# EMG_EEG_PreAmp_Alpha1b.net
KiCad netlist of a schematic drawn in EAGLE
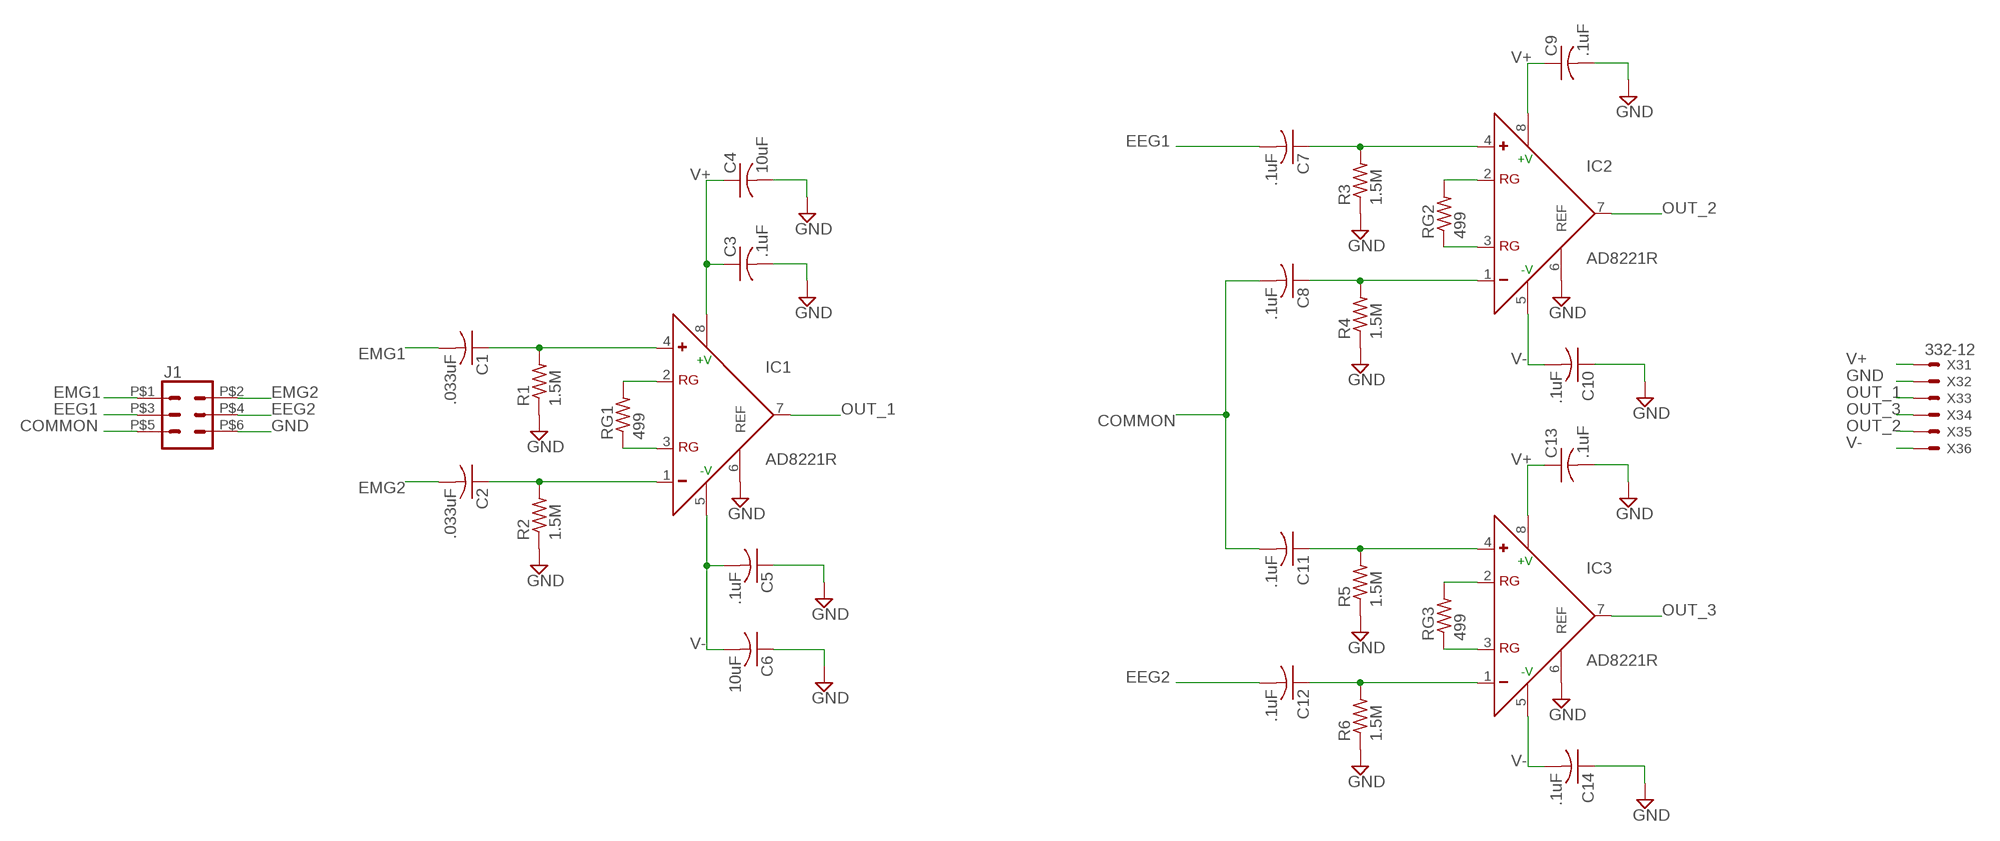
[diagram p0: schematic, sheet 1]

(export (version "E")
  (design (tool "Eeschema 10.0.6"))
  (components
    (comp (ref "C1")
      (value ".033uF")
      (footprint "eagle-import:C0805K")
      (libsource (lib "eagle-import") (part "C-USC0805K"))
    )
    (comp (ref "C2")
      (value ".033uF")
      (footprint "eagle-import:C0805K")
      (libsource (lib "eagle-import") (part "C-USC0805K"))
    )
    (comp (ref "C3")
      (value ".1uF")
      (footprint "eagle-import:C0805K")
      (libsource (lib "eagle-import") (part "C-USC0805K"))
    )
    (comp (ref "C4")
      (value "10uF")
      (footprint "eagle-import:C0805K")
      (libsource (lib "eagle-import") (part "C-USC0805K"))
    )
    (comp (ref "C5")
      (value ".1uF")
      (footprint "eagle-import:C0805K")
      (libsource (lib "eagle-import") (part "C-USC0805K"))
    )
    (comp (ref "C6")
      (value "10uF")
      (footprint "eagle-import:C0805K")
      (libsource (lib "eagle-import") (part "C-USC0805K"))
    )
    (comp (ref "C7")
      (value ".1uF")
      (footprint "eagle-import:C0805K")
      (libsource (lib "eagle-import") (part "C-USC0805K"))
    )
    (comp (ref "C8")
      (value ".1uF")
      (footprint "eagle-import:C0805K")
      (libsource (lib "eagle-import") (part "C-USC0805K"))
    )
    (comp (ref "C9")
      (value ".1uF")
      (footprint "eagle-import:C0805K")
      (libsource (lib "eagle-import") (part "C-USC0805K"))
    )
    (comp (ref "C10")
      (value ".1uF")
      (footprint "eagle-import:C0805K")
      (libsource (lib "eagle-import") (part "C-USC0805K"))
    )
    (comp (ref "C11")
      (value ".1uF")
      (footprint "eagle-import:C0805K")
      (libsource (lib "eagle-import") (part "C-USC0805K"))
    )
    (comp (ref "C12")
      (value ".1uF")
      (footprint "eagle-import:C0805K")
      (libsource (lib "eagle-import") (part "C-USC0805K"))
    )
    (comp (ref "C13")
      (value ".1uF")
      (footprint "eagle-import:C0805K")
      (libsource (lib "eagle-import") (part "C-USC0805K"))
    )
    (comp (ref "C14")
      (value ".1uF")
      (footprint "eagle-import:C0805K")
      (libsource (lib "eagle-import") (part "C-USC0805K"))
    )
    (comp (ref "IC1")
      (value "AD8221R")
      (footprint "eagle-import:SO8")
      (fields (field (name "MPN") "AD620AR"))
      (libsource (lib "eagle-import") (part "AD8221R"))
    )
    (comp (ref "IC2")
      (value "AD8221R")
      (footprint "eagle-import:SO8")
      (fields (field (name "MPN") "AD620AR"))
      (libsource (lib "eagle-import") (part "AD8221R"))
    )
    (comp (ref "IC3")
      (value "AD8221R")
      (footprint "eagle-import:SO8")
      (fields (field (name "MPN") "AD620AR"))
      (libsource (lib "eagle-import") (part "AD8221R"))
    )
    (comp (ref "J1")
      (value "2X3MILL-MAX")
      (footprint "eagle-import:2X3_MILL-MAX_853")
      (libsource (lib "eagle-import") (part "2X3MILL-MAX"))
    )
    (comp (ref "R1")
      (value "1.5M")
      (footprint "eagle-import:R0805")
      (libsource (lib "eagle-import") (part "R-US_R0805"))
    )
    (comp (ref "R2")
      (value "1.5M")
      (footprint "eagle-import:R0805")
      (libsource (lib "eagle-import") (part "R-US_R0805"))
    )
    (comp (ref "R3")
      (value "1.5M")
      (footprint "eagle-import:R0805")
      (libsource (lib "eagle-import") (part "R-US_R0805"))
    )
    (comp (ref "R4")
      (value "1.5M")
      (footprint "eagle-import:R0805")
      (libsource (lib "eagle-import") (part "R-US_R0805"))
    )
    (comp (ref "R5")
      (value "1.5M")
      (footprint "eagle-import:R0805")
      (libsource (lib "eagle-import") (part "R-US_R0805"))
    )
    (comp (ref "R6")
      (value "1.5M")
      (footprint "eagle-import:R0805")
      (libsource (lib "eagle-import") (part "R-US_R0805"))
    )
    (comp (ref "RG1")
      (value "499")
      (footprint "eagle-import:R0805")
      (libsource (lib "eagle-import") (part "R-US_R0805"))
    )
    (comp (ref "RG2")
      (value "499")
      (footprint "eagle-import:R0805")
      (libsource (lib "eagle-import") (part "R-US_R0805"))
    )
    (comp (ref "RG3")
      (value "499")
      (footprint "eagle-import:R0805")
      (libsource (lib "eagle-import") (part "R-US_R0805"))
    )
    (comp (ref "X3")
      (value "332-12")
      (footprint "eagle-import:1X6_WITH_STRAIN_RELIEF")
      (libsource (lib "eagle-import") (part "332-12"))
    )
  )
  (nets
    (net (code "1") (name "/COMMON") (class "Default")
      (node (ref "C11") (pin "2") (pinfunction "2_2") (pintype "passive"))
      (node (ref "C8") (pin "2") (pinfunction "2_2") (pintype "passive"))
      (node (ref "J1") (pin "P$5") (pinfunction "5_P$5") (pintype "bidirectional"))
    )
    (net (code "2") (name "/EEG1") (class "Default")
      (node (ref "C7") (pin "2") (pinfunction "2_2") (pintype "passive"))
      (node (ref "J1") (pin "P$3") (pinfunction "3_P$3") (pintype "bidirectional"))
    )
    (net (code "3") (name "/EEG2") (class "Default")
      (node (ref "C12") (pin "2") (pinfunction "2_2") (pintype "passive"))
      (node (ref "J1") (pin "P$4") (pinfunction "4_P$4") (pintype "bidirectional"))
    )
    (net (code "4") (name "/EMG1") (class "Default")
      (node (ref "C1") (pin "2") (pinfunction "2_2") (pintype "passive"))
      (node (ref "J1") (pin "P$1") (pinfunction "1_P$1") (pintype "bidirectional"))
    )
    (net (code "5") (name "/EMG2") (class "Default")
      (node (ref "C2") (pin "2") (pinfunction "2_2") (pintype "passive"))
      (node (ref "J1") (pin "P$2") (pinfunction "2_P$2") (pintype "bidirectional"))
    )
    (net (code "6") (name "/OUT_1") (class "Default")
      (node (ref "IC1") (pin "7") (pinfunction "OUT_7") (pintype "output"))
      (node (ref "X3") (pin "3") (pinfunction "S_3") (pintype "passive"))
    )
    (net (code "7") (name "/OUT_2") (class "Default")
      (node (ref "IC2") (pin "7") (pinfunction "OUT_7") (pintype "output"))
      (node (ref "X3") (pin "5") (pinfunction "S_5") (pintype "passive"))
    )
    (net (code "8") (name "/OUT_3") (class "Default")
      (node (ref "IC3") (pin "7") (pinfunction "OUT_7") (pintype "output"))
      (node (ref "X3") (pin "4") (pinfunction "S_4") (pintype "passive"))
    )
    (net (code "9") (name "/V+") (class "Default")
      (node (ref "C13") (pin "1") (pinfunction "1_1") (pintype "passive"))
      (node (ref "C3") (pin "1") (pinfunction "1_1") (pintype "passive"))
      (node (ref "C4") (pin "1") (pinfunction "1_1") (pintype "passive"))
      (node (ref "C9") (pin "1") (pinfunction "1_1") (pintype "passive"))
      (node (ref "IC1") (pin "8") (pinfunction "+V_8") (pintype "power_in"))
      (node (ref "IC2") (pin "8") (pinfunction "+V_8") (pintype "power_in"))
      (node (ref "IC3") (pin "8") (pinfunction "+V_8") (pintype "power_in"))
      (node (ref "X3") (pin "1") (pinfunction "S_1") (pintype "passive"))
    )
    (net (code "10") (name "/V-") (class "Default")
      (node (ref "C10") (pin "2") (pinfunction "2_2") (pintype "passive"))
      (node (ref "C14") (pin "2") (pinfunction "2_2") (pintype "passive"))
      (node (ref "C5") (pin "2") (pinfunction "2_2") (pintype "passive"))
      (node (ref "C6") (pin "2") (pinfunction "2_2") (pintype "passive"))
      (node (ref "IC1") (pin "5") (pinfunction "-V_5") (pintype "power_in"))
      (node (ref "IC2") (pin "5") (pinfunction "-V_5") (pintype "power_in"))
      (node (ref "IC3") (pin "5") (pinfunction "-V_5") (pintype "power_in"))
      (node (ref "X3") (pin "6") (pinfunction "S_6") (pintype "passive"))
    )
    (net (code "11") (name "GND") (class "Default")
      (node (ref "C10") (pin "1") (pinfunction "1_1") (pintype "passive"))
      (node (ref "C13") (pin "2") (pinfunction "2_2") (pintype "passive"))
      (node (ref "C14") (pin "1") (pinfunction "1_1") (pintype "passive"))
      (node (ref "C3") (pin "2") (pinfunction "2_2") (pintype "passive"))
      (node (ref "C4") (pin "2") (pinfunction "2_2") (pintype "passive"))
      (node (ref "C5") (pin "1") (pinfunction "1_1") (pintype "passive"))
      (node (ref "C6") (pin "1") (pinfunction "1_1") (pintype "passive"))
      (node (ref "C9") (pin "2") (pinfunction "2_2") (pintype "passive"))
      (node (ref "IC1") (pin "6") (pinfunction "REF_6") (pintype "passive"))
      (node (ref "IC2") (pin "6") (pinfunction "REF_6") (pintype "passive"))
      (node (ref "IC3") (pin "6") (pinfunction "REF_6") (pintype "passive"))
      (node (ref "J1") (pin "P$6") (pinfunction "6_P$6") (pintype "bidirectional"))
      (node (ref "R1") (pin "1") (pinfunction "1_1") (pintype "passive"))
      (node (ref "R2") (pin "1") (pinfunction "1_1") (pintype "passive"))
      (node (ref "R3") (pin "1") (pinfunction "1_1") (pintype "passive"))
      (node (ref "R4") (pin "1") (pinfunction "1_1") (pintype "passive"))
      (node (ref "R5") (pin "1") (pinfunction "1_1") (pintype "passive"))
      (node (ref "R6") (pin "1") (pinfunction "1_1") (pintype "passive"))
      (node (ref "X3") (pin "2") (pinfunction "S_2") (pintype "passive"))
    )
    (net (code "12") (name "Net-(IC1-+)") (class "Default")
      (node (ref "C1") (pin "1") (pinfunction "1_1") (pintype "passive"))
      (node (ref "IC1") (pin "4") (pinfunction "+_4") (pintype "input"))
      (node (ref "R1") (pin "2") (pinfunction "2_2") (pintype "passive"))
    )
    (net (code "13") (name "Net-(IC1--)") (class "Default")
      (node (ref "C2") (pin "1") (pinfunction "1_1") (pintype "passive"))
      (node (ref "IC1") (pin "1") (pinfunction "-_1") (pintype "input"))
      (node (ref "R2") (pin "2") (pinfunction "2_2") (pintype "passive"))
    )
    (net (code "14") (name "Net-(IC1-RG-Pad2)") (class "Default")
      (node (ref "IC1") (pin "2") (pinfunction "RG_2") (pintype "passive"))
      (node (ref "RG1") (pin "2") (pinfunction "2_2") (pintype "passive"))
    )
    (net (code "15") (name "Net-(IC1-RG-Pad3)") (class "Default")
      (node (ref "IC1") (pin "3") (pinfunction "RG_3") (pintype "passive"))
      (node (ref "RG1") (pin "1") (pinfunction "1_1") (pintype "passive"))
    )
    (net (code "16") (name "Net-(IC2-+)") (class "Default")
      (node (ref "C7") (pin "1") (pinfunction "1_1") (pintype "passive"))
      (node (ref "IC2") (pin "4") (pinfunction "+_4") (pintype "input"))
      (node (ref "R3") (pin "2") (pinfunction "2_2") (pintype "passive"))
    )
    (net (code "17") (name "Net-(IC2--)") (class "Default")
      (node (ref "C8") (pin "1") (pinfunction "1_1") (pintype "passive"))
      (node (ref "IC2") (pin "1") (pinfunction "-_1") (pintype "input"))
      (node (ref "R4") (pin "2") (pinfunction "2_2") (pintype "passive"))
    )
    (net (code "18") (name "Net-(IC2-RG-Pad2)") (class "Default")
      (node (ref "IC2") (pin "2") (pinfunction "RG_2") (pintype "passive"))
      (node (ref "RG2") (pin "2") (pinfunction "2_2") (pintype "passive"))
    )
    (net (code "19") (name "Net-(IC2-RG-Pad3)") (class "Default")
      (node (ref "IC2") (pin "3") (pinfunction "RG_3") (pintype "passive"))
      (node (ref "RG2") (pin "1") (pinfunction "1_1") (pintype "passive"))
    )
    (net (code "20") (name "Net-(IC3-+)") (class "Default")
      (node (ref "C11") (pin "1") (pinfunction "1_1") (pintype "passive"))
      (node (ref "IC3") (pin "4") (pinfunction "+_4") (pintype "input"))
      (node (ref "R5") (pin "2") (pinfunction "2_2") (pintype "passive"))
    )
    (net (code "21") (name "Net-(IC3--)") (class "Default")
      (node (ref "C12") (pin "1") (pinfunction "1_1") (pintype "passive"))
      (node (ref "IC3") (pin "1") (pinfunction "-_1") (pintype "input"))
      (node (ref "R6") (pin "2") (pinfunction "2_2") (pintype "passive"))
    )
    (net (code "22") (name "Net-(IC3-RG-Pad2)") (class "Default")
      (node (ref "IC3") (pin "2") (pinfunction "RG_2") (pintype "passive"))
      (node (ref "RG3") (pin "2") (pinfunction "2_2") (pintype "passive"))
    )
    (net (code "23") (name "Net-(IC3-RG-Pad3)") (class "Default")
      (node (ref "IC3") (pin "3") (pinfunction "RG_3") (pintype "passive"))
      (node (ref "RG3") (pin "1") (pinfunction "1_1") (pintype "passive"))
    )
  )
)
